# ADC.net
KiCad netlist of a schematic drawn in Altium Designer
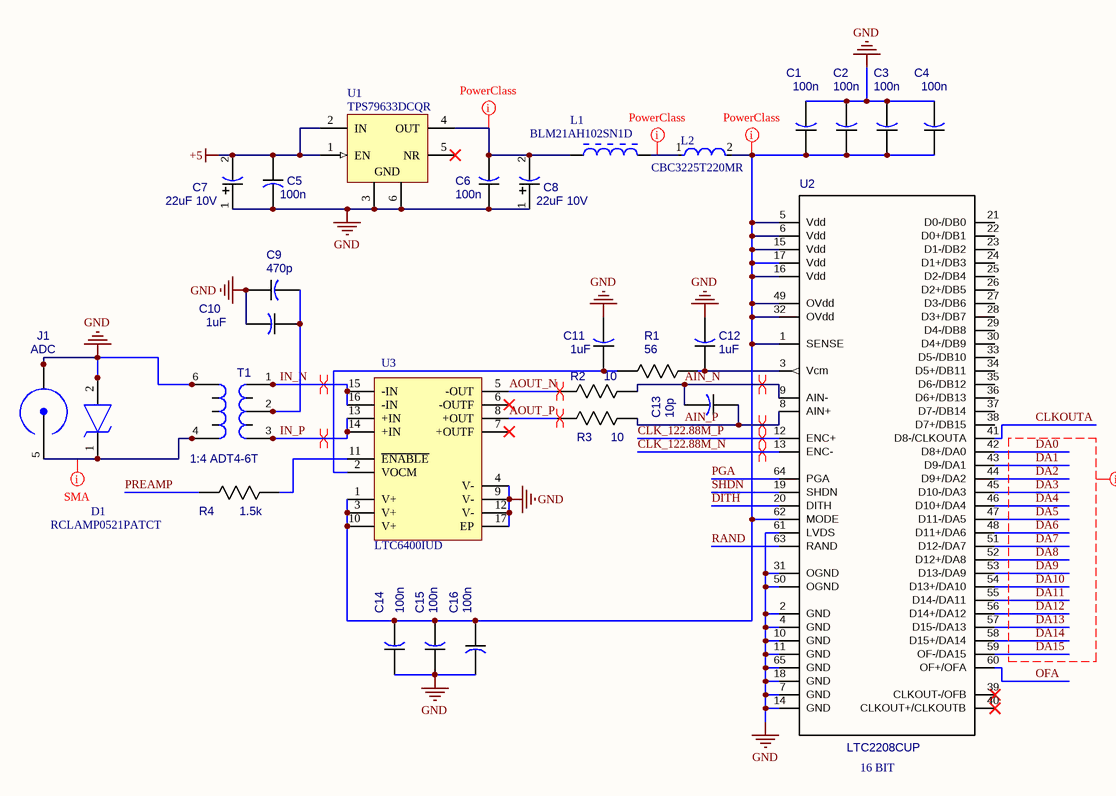
[diagram p0: ADC.SchDoc]

(export (version "E")
  (design (tool "Eeschema 10.0.6"))
  (components
    (comp (ref "C1")
      (value "100n")
      (footprint "CAP_0805")
      (description "CAP_0805")
      (libsource (lib "*") (part "CAP_0805"))
    )
    (comp (ref "C2")
      (value "100n")
      (footprint "CAP_0805")
      (description "CAP_0805")
      (libsource (lib "*") (part "CAP_0805"))
    )
    (comp (ref "C3")
      (value "100n")
      (footprint "CAP_0805")
      (description "CAP_0805")
      (libsource (lib "*") (part "CAP_0805"))
    )
    (comp (ref "C4")
      (value "100n")
      (footprint "CAP_0805")
      (description "CAP_0805")
      (libsource (lib "*") (part "CAP_0805"))
    )
    (comp (ref "C5")
      (value "100n")
      (footprint "CAP_0805")
      (description "CAP_0805")
      (libsource (lib "*") (part "CAP_0805"))
    )
    (comp (ref "C6")
      (value "100n")
      (footprint "CAP_0805")
      (description "CAP_0805")
      (libsource (lib "*") (part "CAP_0805"))
    )
    (comp (ref "C7")
      (value "22uF 10V")
      (footprint "CAPAE_4.3x4.3h5.4")
      (description "CAPAE_4.3x4.3h5.4")
      (libsource (lib "MOTHERBOARD") (part "CAPAE_4.3x4.3h5.4"))
    )
    (comp (ref "C8")
      (value "22uF 10V")
      (footprint "CAPAE_4.3x4.3h5.4")
      (description "CAPAE_4.3x4.3h5.4")
      (libsource (lib "MOTHERBOARD") (part "CAPAE_4.3x4.3h5.4"))
    )
    (comp (ref "C9")
      (value "470p")
      (footprint "CAP_0805")
      (description "CAP_0805")
      (libsource (lib "*") (part "CAP_0805"))
    )
    (comp (ref "C10")
      (value "1uF")
      (footprint "CAP_0805")
      (description "CAP_0805")
      (libsource (lib "*") (part "CAP_0805"))
    )
    (comp (ref "C11")
      (value "1uF")
      (footprint "CAP_0805")
      (description "CAP_0805")
      (libsource (lib "*") (part "CAP_0805"))
    )
    (comp (ref "C12")
      (value "1uF")
      (footprint "CAP_0805")
      (description "CAP_0805")
      (libsource (lib "*") (part "CAP_0805"))
    )
    (comp (ref "C13")
      (value "10p")
      (footprint "CAP_0805")
      (description "CAP_0805")
      (libsource (lib "*") (part "CAP_0805"))
    )
    (comp (ref "C14")
      (value "100n")
      (footprint "CAP_0805")
      (description "CAP_0805")
      (libsource (lib "*") (part "CAP_0805"))
    )
    (comp (ref "C15")
      (value "100n")
      (footprint "CAP_0805")
      (description "CAP_0805")
      (libsource (lib "*") (part "CAP_0805"))
    )
    (comp (ref "C16")
      (value "100n")
      (footprint "CAP_0805")
      (description "CAP_0805")
      (libsource (lib "*") (part "CAP_0805"))
    )
    (comp (ref "D1")
      (value "RCLAMP0521PATCT")
      (footprint "SamacSys:RCLAMP0521PATCT")
      (description "TVS Diode (Uni-directional)")
      (fields (field (name "MOUSER PART NUMBER") "947-RCLAMP0521PATCT"))
      (libsource (lib "SamacSys") (part "RCLAMP0521PATCT"))
    )
    (comp (ref "J1")
      (value "ADC")
      (footprint "31-5431")
      (description "SMA")
      (libsource (lib "RF-UNIT_1") (part "31-5431"))
    )
    (comp (ref "L1")
      (value "BLM21AH102SN1D")
      (footprint "INDC2013X105X50NL20T20")
      (description "Chip Bead, 1000 Ohm, +/- 25%, 200 mA, -55 to 85 degC, 2-Pin SMD, RoHS, Tape and Reel")
      (fields (field (name "MANUFACTURER") "Murata") (field (name "TOLERANCE") "25%"))
      (libsource (lib "Altium Content Vault") (part "IND-FB-2"))
    )
    (comp (ref "L2")
      (value "CBC3225T220MR")
      (footprint "FP-CB3225-IPC_B")
      (description "SMD Inductors 22uH ±20% 0.78A 0.351Ω 1210")
      (fields (field (name "TOLERANCE") "20%"))
      (libsource (lib "Altium Content Vault") (part "725321dda6339637d4d059423bc1c3c"))
    )
    (comp (ref "R1")
      (value "56")
      (footprint "RES_0805")
      (description "RES_0805")
      (libsource (lib "") (part "RES_0805_1"))
    )
    (comp (ref "R2")
      (value "10")
      (footprint "RES_0603")
      (description "RES_0603")
      (libsource (lib "*") (part "RES_0603"))
    )
    (comp (ref "R3")
      (value "10")
      (footprint "RES_0603")
      (description "RES_0603")
      (libsource (lib "*") (part "RES_0603"))
    )
    (comp (ref "R4")
      (value "1.5k")
      (footprint "RES_0805")
      (description "RES_0805")
      (libsource (lib "*") (part "RES_0805"))
    )
    (comp (ref "T1")
      (value "1:4 ADT4-6T")
      (footprint "TRANSF_ACORE2")
      (description "Transformer")
      (libsource (lib "MOTHERBOARD_1") (part "TRANSF_ACORE2"))
    )
    (comp (ref "U1")
      (value "TPS79633DCQR")
      (footprint "DCQ0006A_L")
      (fields (field (name "MANUFACTURER") "Texas Instruments"))
      (libsource (lib "Altium Content Vault") (part "TI-TPS7XXXXXXXX"))
    )
    (comp (ref "U2") (value "LTC2208CUP") (footprint "LTC2208CUP") (libsource (lib "*") (part "LTC2208CUP")))
    (comp (ref "U3")
      (value "LTC6400IUD")
      (footprint "LT-UD-16_N")
      (fields
        (field (name "MANUFACTURER") "Linear Technology")
        (field (name "LINEAR TECHNOLOGY PART NUMBER") "LTC6400-20")
        (field (name "PARTNUMBER") "LTC6400IUD-20#PBF")
      )
      (libsource (lib "Altium Content Vault") (part "LT-LTC640X-X-16"))
    )
  )
  (nets
    (net (code "1") (name "+5") (class "Default")
      (node (ref "C5") (pin "1") (pinfunction "1_1") (pintype "passive"))
      (node (ref "C7") (pin "2") (pinfunction "MINUS_2") (pintype "passive"))
      (node (ref "U1") (pin "1") (pinfunction "EN_1") (pintype "input"))
      (node (ref "U1") (pin "2") (pinfunction "IN_2") (pintype "power_in"))
    )
    (net (code "2") (name "/AIN_N") (class "Default")
      (node (ref "C13") (pin "2") (pinfunction "2_2") (pintype "passive"))
      (node (ref "R2") (pin "2") (pinfunction "2_2") (pintype "passive"))
      (node (ref "U2") (pin "9") (pinfunction "AIN-_9") (pintype "passive"))
    )
    (net (code "3") (name "/AIN_P") (class "Default")
      (node (ref "C13") (pin "1") (pinfunction "1_1") (pintype "passive"))
      (node (ref "R3") (pin "2") (pinfunction "2_2") (pintype "passive"))
      (node (ref "U2") (pin "8") (pinfunction "AIN+_8") (pintype "passive"))
    )
    (net (code "4") (name "/AOUT_N") (class "Default")
      (node (ref "R2") (pin "1") (pinfunction "1_1") (pintype "passive"))
      (node (ref "U3") (pin "5") (pinfunction "-OUT_5") (pintype "passive"))
    )
    (net (code "5") (name "/AOUT_P") (class "Default")
      (node (ref "R3") (pin "1") (pinfunction "1_1") (pintype "passive"))
      (node (ref "U3") (pin "8") (pinfunction "+OUT_8") (pintype "passive"))
    )
    (net (code "6") (name "/CLKOUTA") (class "Default")
      (node (ref "U2") (pin "41") (pinfunction "D8-/CLKOUTA_41") (pintype "passive"))
    )
    (net (code "7") (name "/CLK_122.88M_N") (class "Default")
      (node (ref "U2") (pin "13") (pinfunction "ENC-_13") (pintype "passive"))
    )
    (net (code "8") (name "/CLK_122.88M_P") (class "Default")
      (node (ref "U2") (pin "12") (pinfunction "ENC+_12") (pintype "passive"))
    )
    (net (code "9") (name "/DA0") (class "Default")
      (node (ref "U2") (pin "42") (pinfunction "D8+/DA0_42") (pintype "passive"))
    )
    (net (code "10") (name "/DA1") (class "Default")
      (node (ref "U2") (pin "43") (pinfunction "D9-/DA1_43") (pintype "passive"))
    )
    (net (code "11") (name "/DA2") (class "Default")
      (node (ref "U2") (pin "44") (pinfunction "D9+/DA2_44") (pintype "passive"))
    )
    (net (code "12") (name "/DA3") (class "Default")
      (node (ref "U2") (pin "45") (pinfunction "D10-/DA3_45") (pintype "passive"))
    )
    (net (code "13") (name "/DA4") (class "Default")
      (node (ref "U2") (pin "46") (pinfunction "D10+/DA4_46") (pintype "passive"))
    )
    (net (code "14") (name "/DA5") (class "Default")
      (node (ref "U2") (pin "47") (pinfunction "D11-/DA5_47") (pintype "passive"))
    )
    (net (code "15") (name "/DA6") (class "Default")
      (node (ref "U2") (pin "48") (pinfunction "D11+/DA6_48") (pintype "passive"))
    )
    (net (code "16") (name "/DA7") (class "Default")
      (node (ref "U2") (pin "51") (pinfunction "D12-/DA7_51") (pintype "passive"))
    )
    (net (code "17") (name "/DA8") (class "Default")
      (node (ref "U2") (pin "52") (pinfunction "D12+/DA8_52") (pintype "passive"))
    )
    (net (code "18") (name "/DA9") (class "Default")
      (node (ref "U2") (pin "53") (pinfunction "D13-/DA9_53") (pintype "passive"))
    )
    (net (code "19") (name "/DA10") (class "Default")
      (node (ref "U2") (pin "54") (pinfunction "D13+/DA10_54") (pintype "passive"))
    )
    (net (code "20") (name "/DA11") (class "Default")
      (node (ref "U2") (pin "55") (pinfunction "D14-/DA11_55") (pintype "passive"))
    )
    (net (code "21") (name "/DA12") (class "Default")
      (node (ref "U2") (pin "56") (pinfunction "D14+/DA12_56") (pintype "passive"))
    )
    (net (code "22") (name "/DA13") (class "Default")
      (node (ref "U2") (pin "57") (pinfunction "D15-/DA13_57") (pintype "passive"))
    )
    (net (code "23") (name "/DA14") (class "Default")
      (node (ref "U2") (pin "58") (pinfunction "D15+/DA14_58") (pintype "passive"))
    )
    (net (code "24") (name "/DA15") (class "Default")
      (node (ref "U2") (pin "59") (pinfunction "OF-/DA15_59") (pintype "passive"))
    )
    (net (code "25") (name "/DITH") (class "Default")
      (node (ref "U2") (pin "20") (pinfunction "DITH_20") (pintype "passive"))
    )
    (net (code "26") (name "/IN_N") (class "Default")
      (node (ref "T1") (pin "1") (pinfunction "S3_1") (pintype "passive"))
      (node (ref "T1") (pin "7") (pinfunction "0_7") (pintype "passive"))
      (node (ref "U3") (pin "15") (pinfunction "-IN_15") (pintype "passive"))
      (node (ref "U3") (pin "16") (pinfunction "-IN_16") (pintype "passive"))
    )
    (net (code "27") (name "/IN_P") (class "Default")
      (node (ref "T1") (pin "3") (pinfunction "S1_3") (pintype "passive"))
      (node (ref "T1") (pin "9") (pinfunction "0_9") (pintype "passive"))
      (node (ref "U3") (pin "13") (pinfunction "+IN_13") (pintype "passive"))
      (node (ref "U3") (pin "14") (pinfunction "+IN_14") (pintype "passive"))
    )
    (net (code "28") (name "/OFA") (class "Default")
      (node (ref "U2") (pin "60") (pinfunction "OF+/OFA_60") (pintype "passive"))
    )
    (net (code "29") (name "/PGA") (class "Default")
      (node (ref "U2") (pin "64") (pinfunction "PGA_64") (pintype "passive"))
    )
    (net (code "30") (name "/PREAMP") (class "Default")
      (node (ref "R4") (pin "2") (pinfunction "1_2") (pintype "passive"))
    )
    (net (code "31") (name "/RAND") (class "Default")
      (node (ref "U2") (pin "63") (pinfunction "RAND_63") (pintype "passive"))
    )
    (net (code "32") (name "/SHDN") (class "Default")
      (node (ref "U2") (pin "19") (pinfunction "SHDN_19") (pintype "passive"))
    )
    (net (code "33") (name "GND") (class "Default")
      (node (ref "C1") (pin "2") (pinfunction "2_2") (pintype "passive"))
      (node (ref "C10") (pin "2") (pinfunction "2_2") (pintype "passive"))
      (node (ref "C11") (pin "2") (pinfunction "2_2") (pintype "passive"))
      (node (ref "C12") (pin "2") (pinfunction "2_2") (pintype "passive"))
      (node (ref "C14") (pin "1") (pinfunction "1_1") (pintype "passive"))
      (node (ref "C15") (pin "1") (pinfunction "1_1") (pintype "passive"))
      (node (ref "C16") (pin "2") (pinfunction "2_2") (pintype "passive"))
      (node (ref "C2") (pin "2") (pinfunction "2_2") (pintype "passive"))
      (node (ref "C3") (pin "2") (pinfunction "2_2") (pintype "passive"))
      (node (ref "C4") (pin "2") (pinfunction "2_2") (pintype "passive"))
      (node (ref "C5") (pin "2") (pinfunction "2_2") (pintype "passive"))
      (node (ref "C6") (pin "1") (pinfunction "1_1") (pintype "passive"))
      (node (ref "C7") (pin "1") (pinfunction "PLUS_1") (pintype "passive"))
      (node (ref "C8") (pin "1") (pinfunction "PLUS_1") (pintype "passive"))
      (node (ref "C9") (pin "1") (pinfunction "1_1") (pintype "passive"))
      (node (ref "D1") (pin "2") (pinfunction "A_2") (pintype "passive"))
      (node (ref "J1") (pin "1") (pinfunction "GND_1") (pintype "passive"))
      (node (ref "J1") (pin "2") (pinfunction "GND_2") (pintype "passive"))
      (node (ref "J1") (pin "3") (pinfunction "GND_3") (pintype "passive"))
      (node (ref "J1") (pin "4") (pinfunction "GND_4") (pintype "passive"))
      (node (ref "T1") (pin "10") (pinfunction "0_10") (pintype "passive"))
      (node (ref "T1") (pin "6") (pinfunction "P2_6") (pintype "passive"))
      (node (ref "U1") (pin "3") (pinfunction "GND_3") (pintype "power_in"))
      (node (ref "U1") (pin "6") (pinfunction "GND_6") (pintype "power_in"))
      (node (ref "U2") (pin "10") (pinfunction "GND_10") (pintype "passive"))
      (node (ref "U2") (pin "11") (pinfunction "GND_11") (pintype "passive"))
      (node (ref "U2") (pin "14") (pinfunction "GND_14") (pintype "passive"))
      (node (ref "U2") (pin "18") (pinfunction "GND_18") (pintype "passive"))
      (node (ref "U2") (pin "2") (pinfunction "GND_2") (pintype "passive"))
      (node (ref "U2") (pin "31") (pinfunction "OGND_31") (pintype "passive"))
      (node (ref "U2") (pin "4") (pinfunction "GND_4") (pintype "passive"))
      (node (ref "U2") (pin "50") (pinfunction "OGND_50") (pintype "passive"))
      (node (ref "U2") (pin "61") (pinfunction "LVDS_61") (pintype "passive"))
      (node (ref "U2") (pin "65") (pinfunction "GND_65") (pintype "passive"))
      (node (ref "U2") (pin "7") (pinfunction "GND_7") (pintype "passive"))
      (node (ref "U3") (pin "12") (pinfunction "V-_12") (pintype "power_in"))
      (node (ref "U3") (pin "17") (pinfunction "EP_17") (pintype "power_in"))
      (node (ref "U3") (pin "4") (pinfunction "V-_4") (pintype "power_in"))
      (node (ref "U3") (pin "9") (pinfunction "V-_9") (pintype "power_in"))
    )
    (net (code "34") (name "Net-(C8-MINUS)") (class "Default")
      (node (ref "C6") (pin "2") (pinfunction "2_2") (pintype "passive"))
      (node (ref "C8") (pin "2") (pinfunction "MINUS_2") (pintype "passive"))
      (node (ref "L1") (pin "1") (pinfunction "1_1") (pintype "passive"))
      (node (ref "U1") (pin "4") (pinfunction "OUT_4") (pintype "power_in"))
    )
    (net (code "35") (name "Net-(D1-K)") (class "Default")
      (node (ref "D1") (pin "1") (pinfunction "K_1") (pintype "passive"))
      (node (ref "J1") (pin "5") (pinfunction "CON_5") (pintype "passive"))
      (node (ref "T1") (pin "11") (pinfunction "0_11") (pintype "passive"))
      (node (ref "T1") (pin "4") (pinfunction "P1_4") (pintype "passive"))
    )
    (net (code "36") (name "Net-(L1-Pad2)") (class "Default")
      (node (ref "L1") (pin "2") (pinfunction "2_2") (pintype "passive"))
      (node (ref "L2") (pin "1") (pinfunction "1_1") (pintype "passive"))
    )
    (net (code "37") (name "Net-(R4-2)") (class "Default")
      (node (ref "R4") (pin "1") (pinfunction "2_1") (pintype "passive"))
      (node (ref "U3") (pin "11") (pinfunction "~{ENABLE}_11") (pintype "passive"))
    )
    (net (code "38") (name "Net-(T1-S2)") (class "Default")
      (node (ref "C10") (pin "1") (pinfunction "1_1") (pintype "passive"))
      (node (ref "C9") (pin "2") (pinfunction "2_2") (pintype "passive"))
      (node (ref "T1") (pin "2") (pinfunction "S2_2") (pintype "passive"))
      (node (ref "T1") (pin "8") (pinfunction "0_8") (pintype "passive"))
    )
    (net (code "39") (name "Net-(U2-MODE)") (class "Default")
      (node (ref "C1") (pin "1") (pinfunction "1_1") (pintype "passive"))
      (node (ref "C14") (pin "2") (pinfunction "2_2") (pintype "passive"))
      (node (ref "C15") (pin "2") (pinfunction "2_2") (pintype "passive"))
      (node (ref "C16") (pin "1") (pinfunction "1_1") (pintype "passive"))
      (node (ref "C2") (pin "1") (pinfunction "1_1") (pintype "passive"))
      (node (ref "C3") (pin "1") (pinfunction "1_1") (pintype "passive"))
      (node (ref "C4") (pin "1") (pinfunction "1_1") (pintype "passive"))
      (node (ref "L2") (pin "2") (pinfunction "2_2") (pintype "passive"))
      (node (ref "U2") (pin "1") (pinfunction "SENSE_1") (pintype "passive"))
      (node (ref "U2") (pin "15") (pinfunction "Vdd_15") (pintype "passive"))
      (node (ref "U2") (pin "16") (pinfunction "Vdd_16") (pintype "passive"))
      (node (ref "U2") (pin "17") (pinfunction "Vdd_17") (pintype "passive"))
      (node (ref "U2") (pin "32") (pinfunction "OVdd_32") (pintype "passive"))
      (node (ref "U2") (pin "49") (pinfunction "OVdd_49") (pintype "passive"))
      (node (ref "U2") (pin "5") (pinfunction "Vdd_5") (pintype "passive"))
      (node (ref "U2") (pin "6") (pinfunction "Vdd_6") (pintype "passive"))
      (node (ref "U2") (pin "62") (pinfunction "MODE_62") (pintype "passive"))
      (node (ref "U3") (pin "1") (pinfunction "V+_1") (pintype "power_in"))
      (node (ref "U3") (pin "10") (pinfunction "V+_10") (pintype "power_in"))
      (node (ref "U3") (pin "3") (pinfunction "V+_3") (pintype "power_in"))
    )
    (net (code "40") (name "Net-(U2-Vcm)") (class "Default")
      (node (ref "C12") (pin "1") (pinfunction "1_1") (pintype "passive"))
      (node (ref "R1") (pin "2") (pinfunction "2_2") (pintype "passive"))
      (node (ref "U2") (pin "3") (pinfunction "Vcm_3") (pintype "output"))
    )
    (net (code "41") (name "Net-(U3-VOCM)") (class "Default")
      (node (ref "C11") (pin "1") (pinfunction "1_1") (pintype "passive"))
      (node (ref "R1") (pin "1") (pinfunction "1_1") (pintype "passive"))
      (node (ref "U3") (pin "2") (pinfunction "VOCM_2") (pintype "passive"))
    )
    (net (code "42") (name "unconnected-(U1-NR-Pad5)") (class "Default")
      (node (ref "U1") (pin "5") (pinfunction "NR_5") (pintype "passive+no_connect"))
    )
    (net (code "43") (name "unconnected-(U2-CLKOUT+{slash}CLKOUTB-Pad40)") (class "Default")
      (node (ref "U2") (pin "40") (pinfunction "CLKOUT+/CLKOUTB_40") (pintype "passive+no_connect"))
    )
    (net (code "44") (name "unconnected-(U2-CLKOUT-{slash}OFB-Pad39)") (class "Default")
      (node (ref "U2") (pin "39") (pinfunction "CLKOUT-/OFB_39") (pintype "passive+no_connect"))
    )
    (net (code "45") (name "unconnected-(U2-D0+{slash}DB1-Pad22)") (class "Default")
      (node (ref "U2") (pin "22") (pinfunction "D0+/DB1_22") (pintype "passive"))
    )
    (net (code "46") (name "unconnected-(U2-D0-{slash}DB0-Pad21)") (class "Default")
      (node (ref "U2") (pin "21") (pinfunction "D0-/DB0_21") (pintype "passive"))
    )
    (net (code "47") (name "unconnected-(U2-D1+{slash}DB3-Pad24)") (class "Default")
      (node (ref "U2") (pin "24") (pinfunction "D1+/DB3_24") (pintype "passive"))
    )
    (net (code "48") (name "unconnected-(U2-D1-{slash}DB2-Pad23)") (class "Default")
      (node (ref "U2") (pin "23") (pinfunction "D1-/DB2_23") (pintype "passive"))
    )
    (net (code "49") (name "unconnected-(U2-D2+{slash}DB5-Pad26)") (class "Default")
      (node (ref "U2") (pin "26") (pinfunction "D2+/DB5_26") (pintype "passive"))
    )
    (net (code "50") (name "unconnected-(U2-D2-{slash}DB4-Pad25)") (class "Default")
      (node (ref "U2") (pin "25") (pinfunction "D2-/DB4_25") (pintype "passive"))
    )
    (net (code "51") (name "unconnected-(U2-D3+{slash}DB7-Pad28)") (class "Default")
      (node (ref "U2") (pin "28") (pinfunction "D3+/DB7_28") (pintype "passive"))
    )
    (net (code "52") (name "unconnected-(U2-D3-{slash}DB6-Pad27)") (class "Default")
      (node (ref "U2") (pin "27") (pinfunction "D3-/DB6_27") (pintype "passive"))
    )
    (net (code "53") (name "unconnected-(U2-D4+{slash}DB9-Pad30)") (class "Default")
      (node (ref "U2") (pin "30") (pinfunction "D4+/DB9_30") (pintype "passive"))
    )
    (net (code "54") (name "unconnected-(U2-D4-{slash}DB8-Pad29)") (class "Default")
      (node (ref "U2") (pin "29") (pinfunction "D4-/DB8_29") (pintype "passive"))
    )
    (net (code "55") (name "unconnected-(U2-D5+{slash}DB11-Pad34)") (class "Default")
      (node (ref "U2") (pin "34") (pinfunction "D5+/DB11_34") (pintype "passive"))
    )
    (net (code "56") (name "unconnected-(U2-D5-{slash}DB10-Pad33)") (class "Default")
      (node (ref "U2") (pin "33") (pinfunction "D5-/DB10_33") (pintype "passive"))
    )
    (net (code "57") (name "unconnected-(U2-D6+{slash}DB13-Pad36)") (class "Default")
      (node (ref "U2") (pin "36") (pinfunction "D6+/DB13_36") (pintype "passive"))
    )
    (net (code "58") (name "unconnected-(U2-D6-{slash}DB12-Pad35)") (class "Default")
      (node (ref "U2") (pin "35") (pinfunction "D6-/DB12_35") (pintype "passive"))
    )
    (net (code "59") (name "unconnected-(U2-D7+{slash}DB15-Pad38)") (class "Default")
      (node (ref "U2") (pin "38") (pinfunction "D7+/DB15_38") (pintype "passive"))
    )
    (net (code "60") (name "unconnected-(U2-D7-{slash}DB14-Pad37)") (class "Default")
      (node (ref "U2") (pin "37") (pinfunction "D7-/DB14_37") (pintype "passive"))
    )
    (net (code "61") (name "unconnected-(U3-+OUTF-Pad7)") (class "Default")
      (node (ref "U3") (pin "7") (pinfunction "+OUTF_7") (pintype "passive+no_connect"))
    )
    (net (code "62") (name "unconnected-(U3--OUTF-Pad6)") (class "Default")
      (node (ref "U3") (pin "6") (pinfunction "-OUTF_6") (pintype "passive+no_connect"))
    )
  )
)
